# VCO-revb.net
KiCad netlist of a schematic drawn in EAGLE
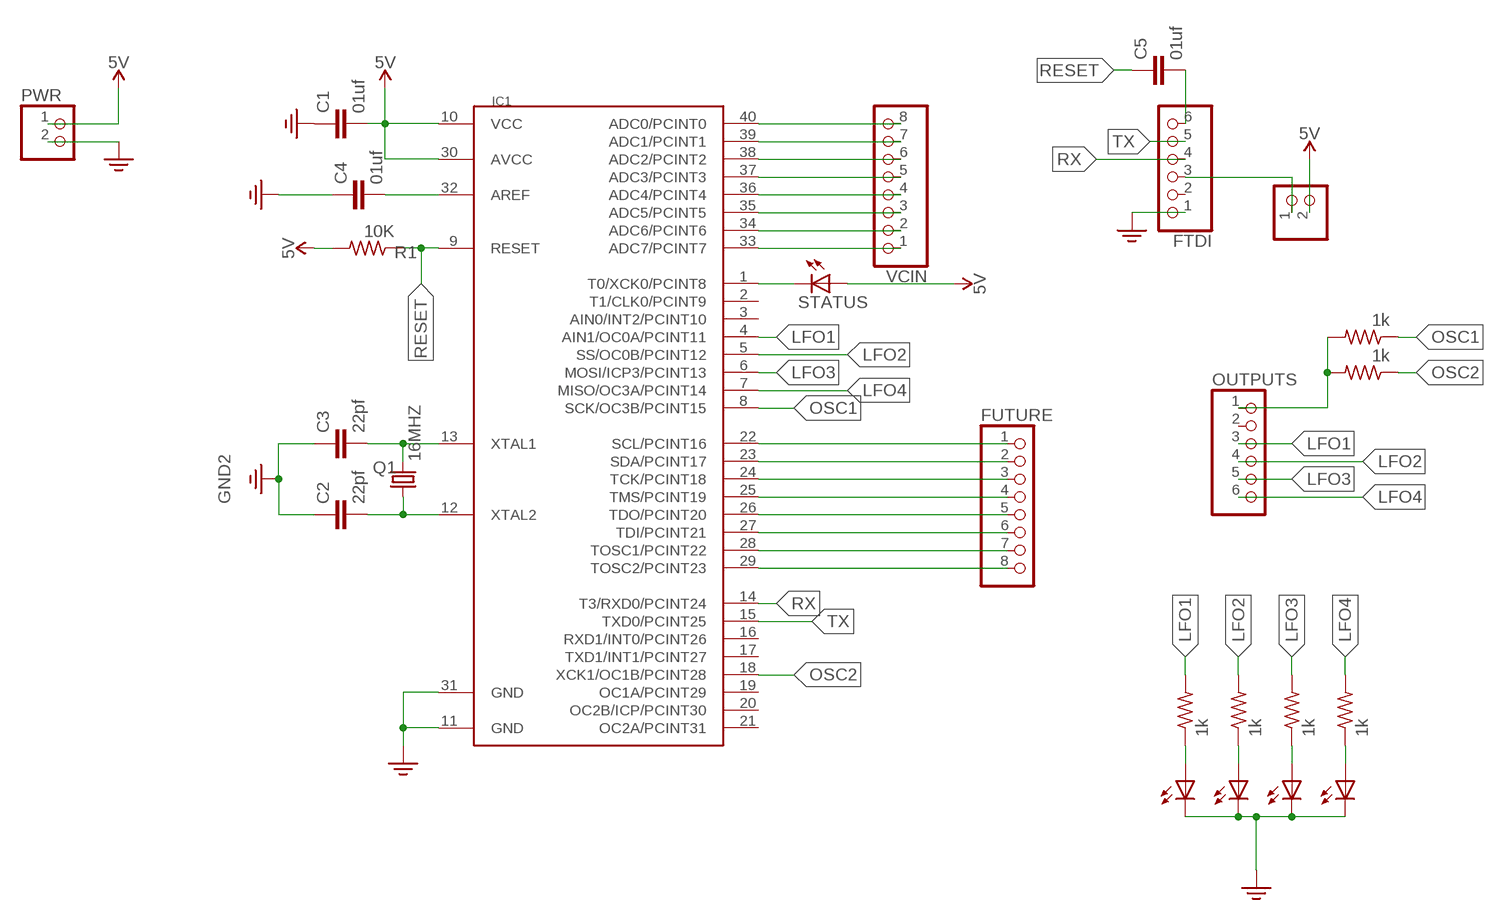
[diagram p0: schematic, sheet 1]

(export (version "E")
  (design (tool "Eeschema 10.0.6"))
  (components
    (comp (ref "C1")
      (value "01uf")
      (footprint "eagle-import:C025-024X044")
      (libsource (lib "eagle-import") (part "C-EU025-024X044"))
    )
    (comp (ref "C2")
      (value "22pf")
      (footprint "eagle-import:C025-024X044")
      (libsource (lib "eagle-import") (part "C-EU025-024X044"))
    )
    (comp (ref "C3")
      (value "22pf")
      (footprint "eagle-import:C025-024X044")
      (libsource (lib "eagle-import") (part "C-EU025-024X044"))
    )
    (comp (ref "C4")
      (value "01uf")
      (footprint "eagle-import:C025-024X044")
      (libsource (lib "eagle-import") (part "C-EU025-024X044"))
    )
    (comp (ref "C5")
      (value "01uf")
      (footprint "eagle-import:C025-024X044")
      (libsource (lib "eagle-import") (part "C-EU025-024X044"))
    )
    (comp (ref "FTDI")
      (value "PINHD-1X6")
      (footprint "eagle-import:1X06")
      (libsource (lib "eagle-import") (part "pinhead_325_PINHD-1X6"))
    )
    (comp (ref "FUTURE")
      (value "PINHD-1X8BIG")
      (footprint "eagle-import:1X08-BIG")
      (libsource (lib "eagle-import") (part "PINHD-1X8BIG"))
    )
    (comp (ref "IC1")
      (value "MEGA1284P")
      (footprint "eagle-import:DIL40")
      (libsource (lib "eagle-import") (part "MEGA1284P"))
    )
    (comp (ref "LFO1")
      (value "LED5MM")
      (footprint "eagle-import:LED5MM")
      (libsource (lib "eagle-import") (part "LED5MM"))
    )
    (comp (ref "LFO2")
      (value "LED5MM")
      (footprint "eagle-import:LED5MM")
      (libsource (lib "eagle-import") (part "LED5MM"))
    )
    (comp (ref "LFO3")
      (value "LED5MM")
      (footprint "eagle-import:LED5MM")
      (libsource (lib "eagle-import") (part "LED5MM"))
    )
    (comp (ref "LFO4")
      (value "LED5MM")
      (footprint "eagle-import:LED5MM")
      (libsource (lib "eagle-import") (part "LED5MM"))
    )
    (comp (ref "OUTPUTS")
      (value "PINHD-1X6")
      (footprint "eagle-import:1X06")
      (libsource (lib "eagle-import") (part "PINHD-1X6"))
    )
    (comp (ref "PWR")
      (value "PINHD-1X2")
      (footprint "eagle-import:1X02")
      (libsource (lib "eagle-import") (part "PINHD-1X2"))
    )
    (comp (ref "PWR1")
      (value "PINHD-1X2")
      (footprint "eagle-import:1X02")
      (libsource (lib "eagle-import") (part "PINHD-1X2"))
    )
    (comp (ref "Q1")
      (value "16MHZ")
      (footprint "eagle-import:HC49_S")
      (libsource (lib "eagle-import") (part "CRYSTALHC49S"))
    )
    (comp (ref "R1")
      (value "10K")
      (footprint "eagle-import:0207_12")
      (libsource (lib "eagle-import") (part "R-US_0207/12"))
    )
    (comp (ref "R2")
      (value "1k")
      (footprint "eagle-import:0207_12")
      (libsource (lib "eagle-import") (part "R-US_0207/12"))
    )
    (comp (ref "R3")
      (value "1k")
      (footprint "eagle-import:0207_12")
      (libsource (lib "eagle-import") (part "R-US_0207/12"))
    )
    (comp (ref "R4")
      (value "1k")
      (footprint "eagle-import:0207_12")
      (libsource (lib "eagle-import") (part "R-US_0207/12"))
    )
    (comp (ref "R5")
      (value "1k")
      (footprint "eagle-import:0207_12")
      (libsource (lib "eagle-import") (part "R-US_0207/12"))
    )
    (comp (ref "R6")
      (value "1k")
      (footprint "eagle-import:0207_12")
      (libsource (lib "eagle-import") (part "R-US_0207/12"))
    )
    (comp (ref "R7")
      (value "1k")
      (footprint "eagle-import:0207_12")
      (libsource (lib "eagle-import") (part "R-US_0207/12"))
    )
    (comp (ref "STATUS")
      (value "LED5MM")
      (footprint "eagle-import:LED5MM")
      (libsource (lib "eagle-import") (part "LED5MM"))
    )
    (comp (ref "VCIN")
      (value "PINHD-1X8")
      (footprint "eagle-import:1X08")
      (libsource (lib "eagle-import") (part "PINHD-1X8"))
    )
  )
  (nets
    (net (code "1") (name "5V") (class "Default")
      (node (ref "C1") (pin "2") (pinfunction "2_2") (pintype "passive"))
      (node (ref "IC1") (pin "10") (pinfunction "VCC_10") (pintype "bidirectional"))
      (node (ref "IC1") (pin "30") (pinfunction "AVCC_30") (pintype "bidirectional"))
      (node (ref "PWR") (pin "1") (pinfunction "1_1") (pintype "passive"))
      (node (ref "PWR1") (pin "2") (pinfunction "2_2") (pintype "passive"))
      (node (ref "R1") (pin "2") (pinfunction "2_2") (pintype "passive"))
      (node (ref "STATUS") (pin "A") (pinfunction "A_A") (pintype "passive"))
    )
    (net (code "2") (name "GND2") (class "Default")
      (node (ref "C1") (pin "1") (pinfunction "1_1") (pintype "passive"))
      (node (ref "C2") (pin "1") (pinfunction "1_1") (pintype "passive"))
      (node (ref "C3") (pin "1") (pinfunction "1_1") (pintype "passive"))
      (node (ref "C4") (pin "1") (pinfunction "1_1") (pintype "passive"))
      (node (ref "FTDI") (pin "1") (pinfunction "1_1") (pintype "passive"))
      (node (ref "IC1") (pin "11") (pinfunction "GND_11") (pintype "bidirectional"))
      (node (ref "IC1") (pin "31") (pinfunction "GND_31") (pintype "bidirectional"))
      (node (ref "LFO1") (pin "K") (pinfunction "C_K") (pintype "passive"))
      (node (ref "LFO2") (pin "K") (pinfunction "C_K") (pintype "passive"))
      (node (ref "LFO3") (pin "K") (pinfunction "C_K") (pintype "passive"))
      (node (ref "LFO4") (pin "K") (pinfunction "C_K") (pintype "passive"))
      (node (ref "PWR") (pin "2") (pinfunction "2_2") (pintype "passive"))
    )
    (net (code "3") (name "LFO1") (class "Default")
      (node (ref "IC1") (pin "4") (pinfunction "AIN1/OC0A/PCINT11_4") (pintype "bidirectional"))
      (node (ref "OUTPUTS") (pin "3") (pinfunction "3_3") (pintype "passive"))
      (node (ref "R4") (pin "2") (pinfunction "2_2") (pintype "passive"))
    )
    (net (code "4") (name "LFO2") (class "Default")
      (node (ref "IC1") (pin "5") (pinfunction "SS/OC0B/PCINT12_5") (pintype "bidirectional"))
      (node (ref "OUTPUTS") (pin "4") (pinfunction "4_4") (pintype "passive"))
      (node (ref "R3") (pin "2") (pinfunction "2_2") (pintype "passive"))
    )
    (net (code "5") (name "LFO3") (class "Default")
      (node (ref "IC1") (pin "6") (pinfunction "MOSI/ICP3/PCINT13_6") (pintype "bidirectional"))
      (node (ref "OUTPUTS") (pin "5") (pinfunction "5_5") (pintype "passive"))
      (node (ref "R2") (pin "2") (pinfunction "2_2") (pintype "passive"))
    )
    (net (code "6") (name "LFO4") (class "Default")
      (node (ref "IC1") (pin "7") (pinfunction "MISO/OC3A/PCINT14_7") (pintype "bidirectional"))
      (node (ref "OUTPUTS") (pin "6") (pinfunction "6_6") (pintype "passive"))
      (node (ref "R5") (pin "2") (pinfunction "2_2") (pintype "passive"))
    )
    (net (code "7") (name "Net-(C5-Pad2)") (class "Default")
      (node (ref "C5") (pin "2") (pinfunction "2_2") (pintype "passive"))
      (node (ref "FTDI") (pin "6") (pinfunction "6_6") (pintype "passive"))
    )
    (net (code "8") (name "Net-(FTDI-Pad3)") (class "Default")
      (node (ref "FTDI") (pin "3") (pinfunction "3_3") (pintype "passive"))
      (node (ref "PWR1") (pin "1") (pinfunction "1_1") (pintype "passive"))
    )
    (net (code "9") (name "Net-(IC1-ADC0{slash}PCINT0)") (class "Default")
      (node (ref "IC1") (pin "40") (pinfunction "ADC0/PCINT0_40") (pintype "bidirectional"))
      (node (ref "VCIN") (pin "8") (pinfunction "8_8") (pintype "passive"))
    )
    (net (code "10") (name "Net-(IC1-ADC1{slash}PCINT1)") (class "Default")
      (node (ref "IC1") (pin "39") (pinfunction "ADC1/PCINT1_39") (pintype "bidirectional"))
      (node (ref "VCIN") (pin "7") (pinfunction "7_7") (pintype "passive"))
    )
    (net (code "11") (name "Net-(IC1-ADC2{slash}PCINT2)") (class "Default")
      (node (ref "IC1") (pin "38") (pinfunction "ADC2/PCINT2_38") (pintype "bidirectional"))
      (node (ref "VCIN") (pin "6") (pinfunction "6_6") (pintype "passive"))
    )
    (net (code "12") (name "Net-(IC1-ADC3{slash}PCINT3)") (class "Default")
      (node (ref "IC1") (pin "37") (pinfunction "ADC3/PCINT3_37") (pintype "bidirectional"))
      (node (ref "VCIN") (pin "5") (pinfunction "5_5") (pintype "passive"))
    )
    (net (code "13") (name "Net-(IC1-ADC4{slash}PCINT4)") (class "Default")
      (node (ref "IC1") (pin "36") (pinfunction "ADC4/PCINT4_36") (pintype "bidirectional"))
      (node (ref "VCIN") (pin "4") (pinfunction "4_4") (pintype "passive"))
    )
    (net (code "14") (name "Net-(IC1-ADC5{slash}PCINT5)") (class "Default")
      (node (ref "IC1") (pin "35") (pinfunction "ADC5/PCINT5_35") (pintype "bidirectional"))
      (node (ref "VCIN") (pin "3") (pinfunction "3_3") (pintype "passive"))
    )
    (net (code "15") (name "Net-(IC1-ADC6{slash}PCINT6)") (class "Default")
      (node (ref "IC1") (pin "34") (pinfunction "ADC6/PCINT6_34") (pintype "bidirectional"))
      (node (ref "VCIN") (pin "2") (pinfunction "2_2") (pintype "passive"))
    )
    (net (code "16") (name "Net-(IC1-ADC7{slash}PCINT7)") (class "Default")
      (node (ref "IC1") (pin "33") (pinfunction "ADC7/PCINT7_33") (pintype "bidirectional"))
      (node (ref "VCIN") (pin "1") (pinfunction "1_1") (pintype "passive"))
    )
    (net (code "17") (name "Net-(IC1-AREF)") (class "Default")
      (node (ref "C4") (pin "2") (pinfunction "2_2") (pintype "passive"))
      (node (ref "IC1") (pin "32") (pinfunction "AREF_32") (pintype "bidirectional"))
    )
    (net (code "18") (name "Net-(IC1-SCL{slash}PCINT16)") (class "Default")
      (node (ref "FUTURE") (pin "1") (pinfunction "1_1") (pintype "passive"))
      (node (ref "IC1") (pin "22") (pinfunction "SCL/PCINT16_22") (pintype "bidirectional"))
    )
    (net (code "19") (name "Net-(IC1-SDA{slash}PCINT17)") (class "Default")
      (node (ref "FUTURE") (pin "2") (pinfunction "2_2") (pintype "passive"))
      (node (ref "IC1") (pin "23") (pinfunction "SDA/PCINT17_23") (pintype "bidirectional"))
    )
    (net (code "20") (name "Net-(IC1-T0{slash}XCK0{slash}PCINT8)") (class "Default")
      (node (ref "IC1") (pin "1") (pinfunction "T0/XCK0/PCINT8_1") (pintype "bidirectional"))
      (node (ref "STATUS") (pin "K") (pinfunction "C_K") (pintype "passive"))
    )
    (net (code "21") (name "Net-(IC1-TCK{slash}PCINT18)") (class "Default")
      (node (ref "FUTURE") (pin "3") (pinfunction "3_3") (pintype "passive"))
      (node (ref "IC1") (pin "24") (pinfunction "TCK/PCINT18_24") (pintype "bidirectional"))
    )
    (net (code "22") (name "Net-(IC1-TDI{slash}PCINT21)") (class "Default")
      (node (ref "FUTURE") (pin "6") (pinfunction "6_6") (pintype "passive"))
      (node (ref "IC1") (pin "27") (pinfunction "TDI/PCINT21_27") (pintype "bidirectional"))
    )
    (net (code "23") (name "Net-(IC1-TDO{slash}PCINT20)") (class "Default")
      (node (ref "FUTURE") (pin "5") (pinfunction "5_5") (pintype "passive"))
      (node (ref "IC1") (pin "26") (pinfunction "TDO/PCINT20_26") (pintype "bidirectional"))
    )
    (net (code "24") (name "Net-(IC1-TMS{slash}PCINT19)") (class "Default")
      (node (ref "FUTURE") (pin "4") (pinfunction "4_4") (pintype "passive"))
      (node (ref "IC1") (pin "25") (pinfunction "TMS/PCINT19_25") (pintype "bidirectional"))
    )
    (net (code "25") (name "Net-(IC1-TOSC1{slash}PCINT22)") (class "Default")
      (node (ref "FUTURE") (pin "7") (pinfunction "7_7") (pintype "passive"))
      (node (ref "IC1") (pin "28") (pinfunction "TOSC1/PCINT22_28") (pintype "bidirectional"))
    )
    (net (code "26") (name "Net-(IC1-TOSC2{slash}PCINT23)") (class "Default")
      (node (ref "FUTURE") (pin "8") (pinfunction "8_8") (pintype "passive"))
      (node (ref "IC1") (pin "29") (pinfunction "TOSC2/PCINT23_29") (pintype "bidirectional"))
    )
    (net (code "27") (name "Net-(IC1-XTAL1)") (class "Default")
      (node (ref "C3") (pin "2") (pinfunction "2_2") (pintype "passive"))
      (node (ref "IC1") (pin "13") (pinfunction "XTAL1_13") (pintype "bidirectional"))
      (node (ref "Q1") (pin "2") (pinfunction "2_2") (pintype "passive"))
    )
    (net (code "28") (name "Net-(IC1-XTAL2)") (class "Default")
      (node (ref "C2") (pin "2") (pinfunction "2_2") (pintype "passive"))
      (node (ref "IC1") (pin "12") (pinfunction "XTAL2_12") (pintype "bidirectional"))
      (node (ref "Q1") (pin "1") (pinfunction "1_1") (pintype "passive"))
    )
    (net (code "29") (name "Net-(LFO1-PadA)") (class "Default")
      (node (ref "LFO1") (pin "A") (pinfunction "A_A") (pintype "passive"))
      (node (ref "R4") (pin "1") (pinfunction "1_1") (pintype "passive"))
    )
    (net (code "30") (name "Net-(LFO2-PadA)") (class "Default")
      (node (ref "LFO2") (pin "A") (pinfunction "A_A") (pintype "passive"))
      (node (ref "R3") (pin "1") (pinfunction "1_1") (pintype "passive"))
    )
    (net (code "31") (name "Net-(LFO3-PadA)") (class "Default")
      (node (ref "LFO3") (pin "A") (pinfunction "A_A") (pintype "passive"))
      (node (ref "R2") (pin "1") (pinfunction "1_1") (pintype "passive"))
    )
    (net (code "32") (name "Net-(LFO4-PadA)") (class "Default")
      (node (ref "LFO4") (pin "A") (pinfunction "A_A") (pintype "passive"))
      (node (ref "R5") (pin "1") (pinfunction "1_1") (pintype "passive"))
    )
    (net (code "33") (name "Net-(OUTPUTS-Pad1)") (class "Default")
      (node (ref "OUTPUTS") (pin "1") (pinfunction "1_1") (pintype "passive"))
      (node (ref "R6") (pin "2") (pinfunction "2_2") (pintype "passive"))
      (node (ref "R7") (pin "2") (pinfunction "2_2") (pintype "passive"))
    )
    (net (code "34") (name "OSC1") (class "Default")
      (node (ref "IC1") (pin "8") (pinfunction "SCK/OC3B/PCINT15_8") (pintype "bidirectional"))
      (node (ref "R6") (pin "1") (pinfunction "1_1") (pintype "passive"))
    )
    (net (code "35") (name "OSC2") (class "Default")
      (node (ref "IC1") (pin "18") (pinfunction "XCK1/OC1B/PCINT28_18") (pintype "bidirectional"))
      (node (ref "R7") (pin "1") (pinfunction "1_1") (pintype "passive"))
    )
    (net (code "36") (name "RESET") (class "Default")
      (node (ref "C5") (pin "1") (pinfunction "1_1") (pintype "passive"))
      (node (ref "IC1") (pin "9") (pinfunction "RESET_9") (pintype "bidirectional"))
      (node (ref "R1") (pin "1") (pinfunction "1_1") (pintype "passive"))
    )
    (net (code "37") (name "RX") (class "Default")
      (node (ref "FTDI") (pin "4") (pinfunction "4_4") (pintype "passive"))
      (node (ref "IC1") (pin "14") (pinfunction "T3/RXD0/PCINT24_14") (pintype "bidirectional"))
    )
    (net (code "38") (name "TX") (class "Default")
      (node (ref "FTDI") (pin "5") (pinfunction "5_5") (pintype "passive"))
      (node (ref "IC1") (pin "15") (pinfunction "TXD0/PCINT25_15") (pintype "bidirectional"))
    )
    (net (code "39") (name "unconnected-(FTDI-Pad2)") (class "Default")
      (node (ref "FTDI") (pin "2") (pinfunction "2_2") (pintype "passive"))
    )
    (net (code "40") (name "unconnected-(IC1-AIN0{slash}INT2{slash}PCINT10-Pad3)") (class "Default")
      (node (ref "IC1") (pin "3") (pinfunction "AIN0/INT2/PCINT10_3") (pintype "bidirectional"))
    )
    (net (code "41") (name "unconnected-(IC1-OC1A{slash}PCINT29-Pad19)") (class "Default")
      (node (ref "IC1") (pin "19") (pinfunction "OC1A/PCINT29_19") (pintype "bidirectional"))
    )
    (net (code "42") (name "unconnected-(IC1-OC2A{slash}PCINT31-Pad21)") (class "Default")
      (node (ref "IC1") (pin "21") (pinfunction "OC2A/PCINT31_21") (pintype "bidirectional"))
    )
    (net (code "43") (name "unconnected-(IC1-OC2B{slash}ICP{slash}PCINT30-Pad20)") (class "Default")
      (node (ref "IC1") (pin "20") (pinfunction "OC2B/ICP/PCINT30_20") (pintype "bidirectional"))
    )
    (net (code "44") (name "unconnected-(IC1-RXD1{slash}INT0{slash}PCINT26-Pad16)") (class "Default")
      (node (ref "IC1") (pin "16") (pinfunction "RXD1/INT0/PCINT26_16") (pintype "bidirectional"))
    )
    (net (code "45") (name "unconnected-(IC1-T1{slash}CLK0{slash}PCINT9-Pad2)") (class "Default")
      (node (ref "IC1") (pin "2") (pinfunction "T1/CLK0/PCINT9_2") (pintype "bidirectional"))
    )
    (net (code "46") (name "unconnected-(IC1-TXD1{slash}INT1{slash}PCINT27-Pad17)") (class "Default")
      (node (ref "IC1") (pin "17") (pinfunction "TXD1/INT1/PCINT27_17") (pintype "bidirectional"))
    )
    (net (code "47") (name "unconnected-(OUTPUTS-Pad2)") (class "Default")
      (node (ref "OUTPUTS") (pin "2") (pinfunction "2_2") (pintype "passive"))
    )
  )
)
